# DepthSensor.net
KiCad netlist of a schematic drawn in Altium Designer
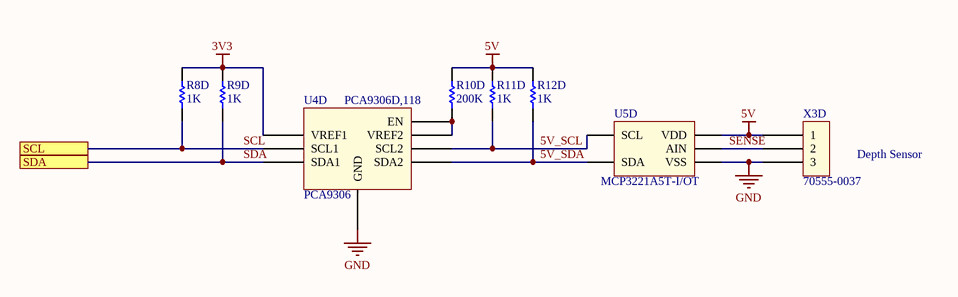
[diagram p0: DepthSensor.SchDoc]

(export (version "E")
  (design (tool "Eeschema 10.0.6"))
  (components
    (comp (ref "R8D")
      (value "1K")
      (footprint "RESC1206(3216)_N")
      (description "1K 0.25W 1% 1206 (3216 Metric)  SMD")
      (fields (field (name "POWER") "0.25 W") (field (name "TOLERANCE") "1 %"))
      (libsource (lib "Altium Content Vault") (part "RES"))
    )
    (comp (ref "R9D")
      (value "1K")
      (footprint "RESC1206(3216)_N")
      (description "1K 0.25W 1% 1206 (3216 Metric)  SMD")
      (fields (field (name "POWER") "0.25 W") (field (name "TOLERANCE") "1 %"))
      (libsource (lib "Altium Content Vault") (part "RES"))
    )
    (comp (ref "R10D")
      (value "200K")
      (footprint "RESC1206(3216)_M")
      (description "200K 0.25W 1% 1206 (3216 Metric)  SMD")
      (fields (field (name "POWER") "0.25 W") (field (name "TOLERANCE") "1 %"))
      (libsource (lib "Altium Content Vault") (part "RES"))
    )
    (comp (ref "R11D")
      (value "1K")
      (footprint "RESC1206(3216)_N")
      (description "1K 0.25W 1% 1206 (3216 Metric)  SMD")
      (fields (field (name "POWER") "0.25 W") (field (name "TOLERANCE") "1 %"))
      (libsource (lib "Altium Content Vault") (part "RES"))
    )
    (comp (ref "R12D")
      (value "1K")
      (footprint "RESC1206(3216)_N")
      (description "1K 0.25W 1% 1206 (3216 Metric)  SMD")
      (fields (field (name "POWER") "0.25 W") (field (name "TOLERANCE") "1 %"))
      (libsource (lib "Altium Content Vault") (part "RES"))
    )
    (comp (ref "U4D")
      (value "PCA9306")
      (footprint "PCA9306-SO8")
      (description "PCA9306, Bidirectional level translator")
      (fields (field (name "MANUFACTURER") "NXP") (field (name "MANUFACTURER PART NUMBER") "PCA9306D,118"))
      (libsource (lib "URC") (part "PCA9306"))
    )
    (comp (ref "U5D")
      (value "~")
      (footprint "MCP3221-SOT23-5")
      (description "MCP3221, 12 bit ADC, I2C")
      (fields
        (field (name "MANUFACTURER") "MICROCHIP")
        (field (name "MANUFACTURER PART NUMBER") "MCP3221A5T-I/OT")
      )
      (libsource (lib "URC") (part "MCP3221"))
    )
    (comp (ref "X3D")
      (value "70555-0037")
      (footprint "70555-0037")
      (description "Molex, C-Grid SL 70555, 3 Pin")
      (fields (field (name "MANUFACTURER") "MOLEX"))
      (libsource (lib "URC") (part "70555-0037"))
    )
  )
  (nets
    (net (code "1") (name "/5V_SCL") (class "Default")
      (node (ref "R11D") (pin "1") (pinfunction "1_1") (pintype "passive"))
      (node (ref "U4D") (pin "SCL2") (pinfunction "SCL2_SCL2") (pintype "passive"))
      (node (ref "U5D") (pin "SCL") (pinfunction "SCL_SCL") (pintype "passive"))
    )
    (net (code "2") (name "/5V_SDA") (class "Default")
      (node (ref "R12D") (pin "1") (pinfunction "1_1") (pintype "passive"))
      (node (ref "U4D") (pin "SDA2") (pinfunction "SDA2_SDA2") (pintype "passive"))
      (node (ref "U5D") (pin "SDA") (pinfunction "SDA_SDA") (pintype "passive"))
    )
    (net (code "3") (name "/SCL") (class "Default")
      (node (ref "R8D") (pin "1") (pinfunction "1_1") (pintype "passive"))
      (node (ref "U4D") (pin "SCL1") (pinfunction "SCL1_SCL1") (pintype "passive"))
    )
    (net (code "4") (name "/SDA") (class "Default")
      (node (ref "R9D") (pin "1") (pinfunction "1_1") (pintype "passive"))
      (node (ref "U4D") (pin "SDA1") (pinfunction "SDA1_SDA1") (pintype "passive"))
    )
    (net (code "5") (name "/SENSE") (class "Default")
      (node (ref "U5D") (pin "AIN") (pinfunction "AIN_AIN") (pintype "passive"))
      (node (ref "X3D") (pin "2") (pinfunction "2_2") (pintype "passive"))
    )
    (net (code "6") (name "3V3") (class "Default")
      (node (ref "R8D") (pin "2") (pinfunction "2_2") (pintype "passive"))
      (node (ref "R9D") (pin "2") (pinfunction "2_2") (pintype "passive"))
      (node (ref "U4D") (pin "VREF1") (pinfunction "VREF1_VREF1") (pintype "passive"))
    )
    (net (code "7") (name "5V") (class "Default")
      (node (ref "R10D") (pin "2") (pinfunction "2_2") (pintype "passive"))
      (node (ref "R11D") (pin "2") (pinfunction "2_2") (pintype "passive"))
      (node (ref "R12D") (pin "2") (pinfunction "2_2") (pintype "passive"))
      (node (ref "U5D") (pin "VDD") (pinfunction "VDD_VDD") (pintype "passive"))
      (node (ref "X3D") (pin "1") (pinfunction "1_1") (pintype "passive"))
    )
    (net (code "8") (name "GND") (class "Default")
      (node (ref "U4D") (pin "GND") (pinfunction "GND_GND") (pintype "passive"))
      (node (ref "U5D") (pin "VSS") (pinfunction "VSS_VSS") (pintype "passive"))
      (node (ref "X3D") (pin "3") (pinfunction "3_3") (pintype "passive"))
    )
    (net (code "9") (name "Net-(R10D-Pad1)") (class "Default")
      (node (ref "R10D") (pin "1") (pinfunction "1_1") (pintype "passive"))
      (node (ref "U4D") (pin "EN") (pinfunction "EN_EN") (pintype "passive"))
      (node (ref "U4D") (pin "VREF2") (pinfunction "VREF2_VREF2") (pintype "passive"))
    )
  )
)
